# EasyEDA_SCH_BL28Z-3005ZSK04Y_K_Version_B.net
KiCad netlist of a schematic drawn in EasyEDA
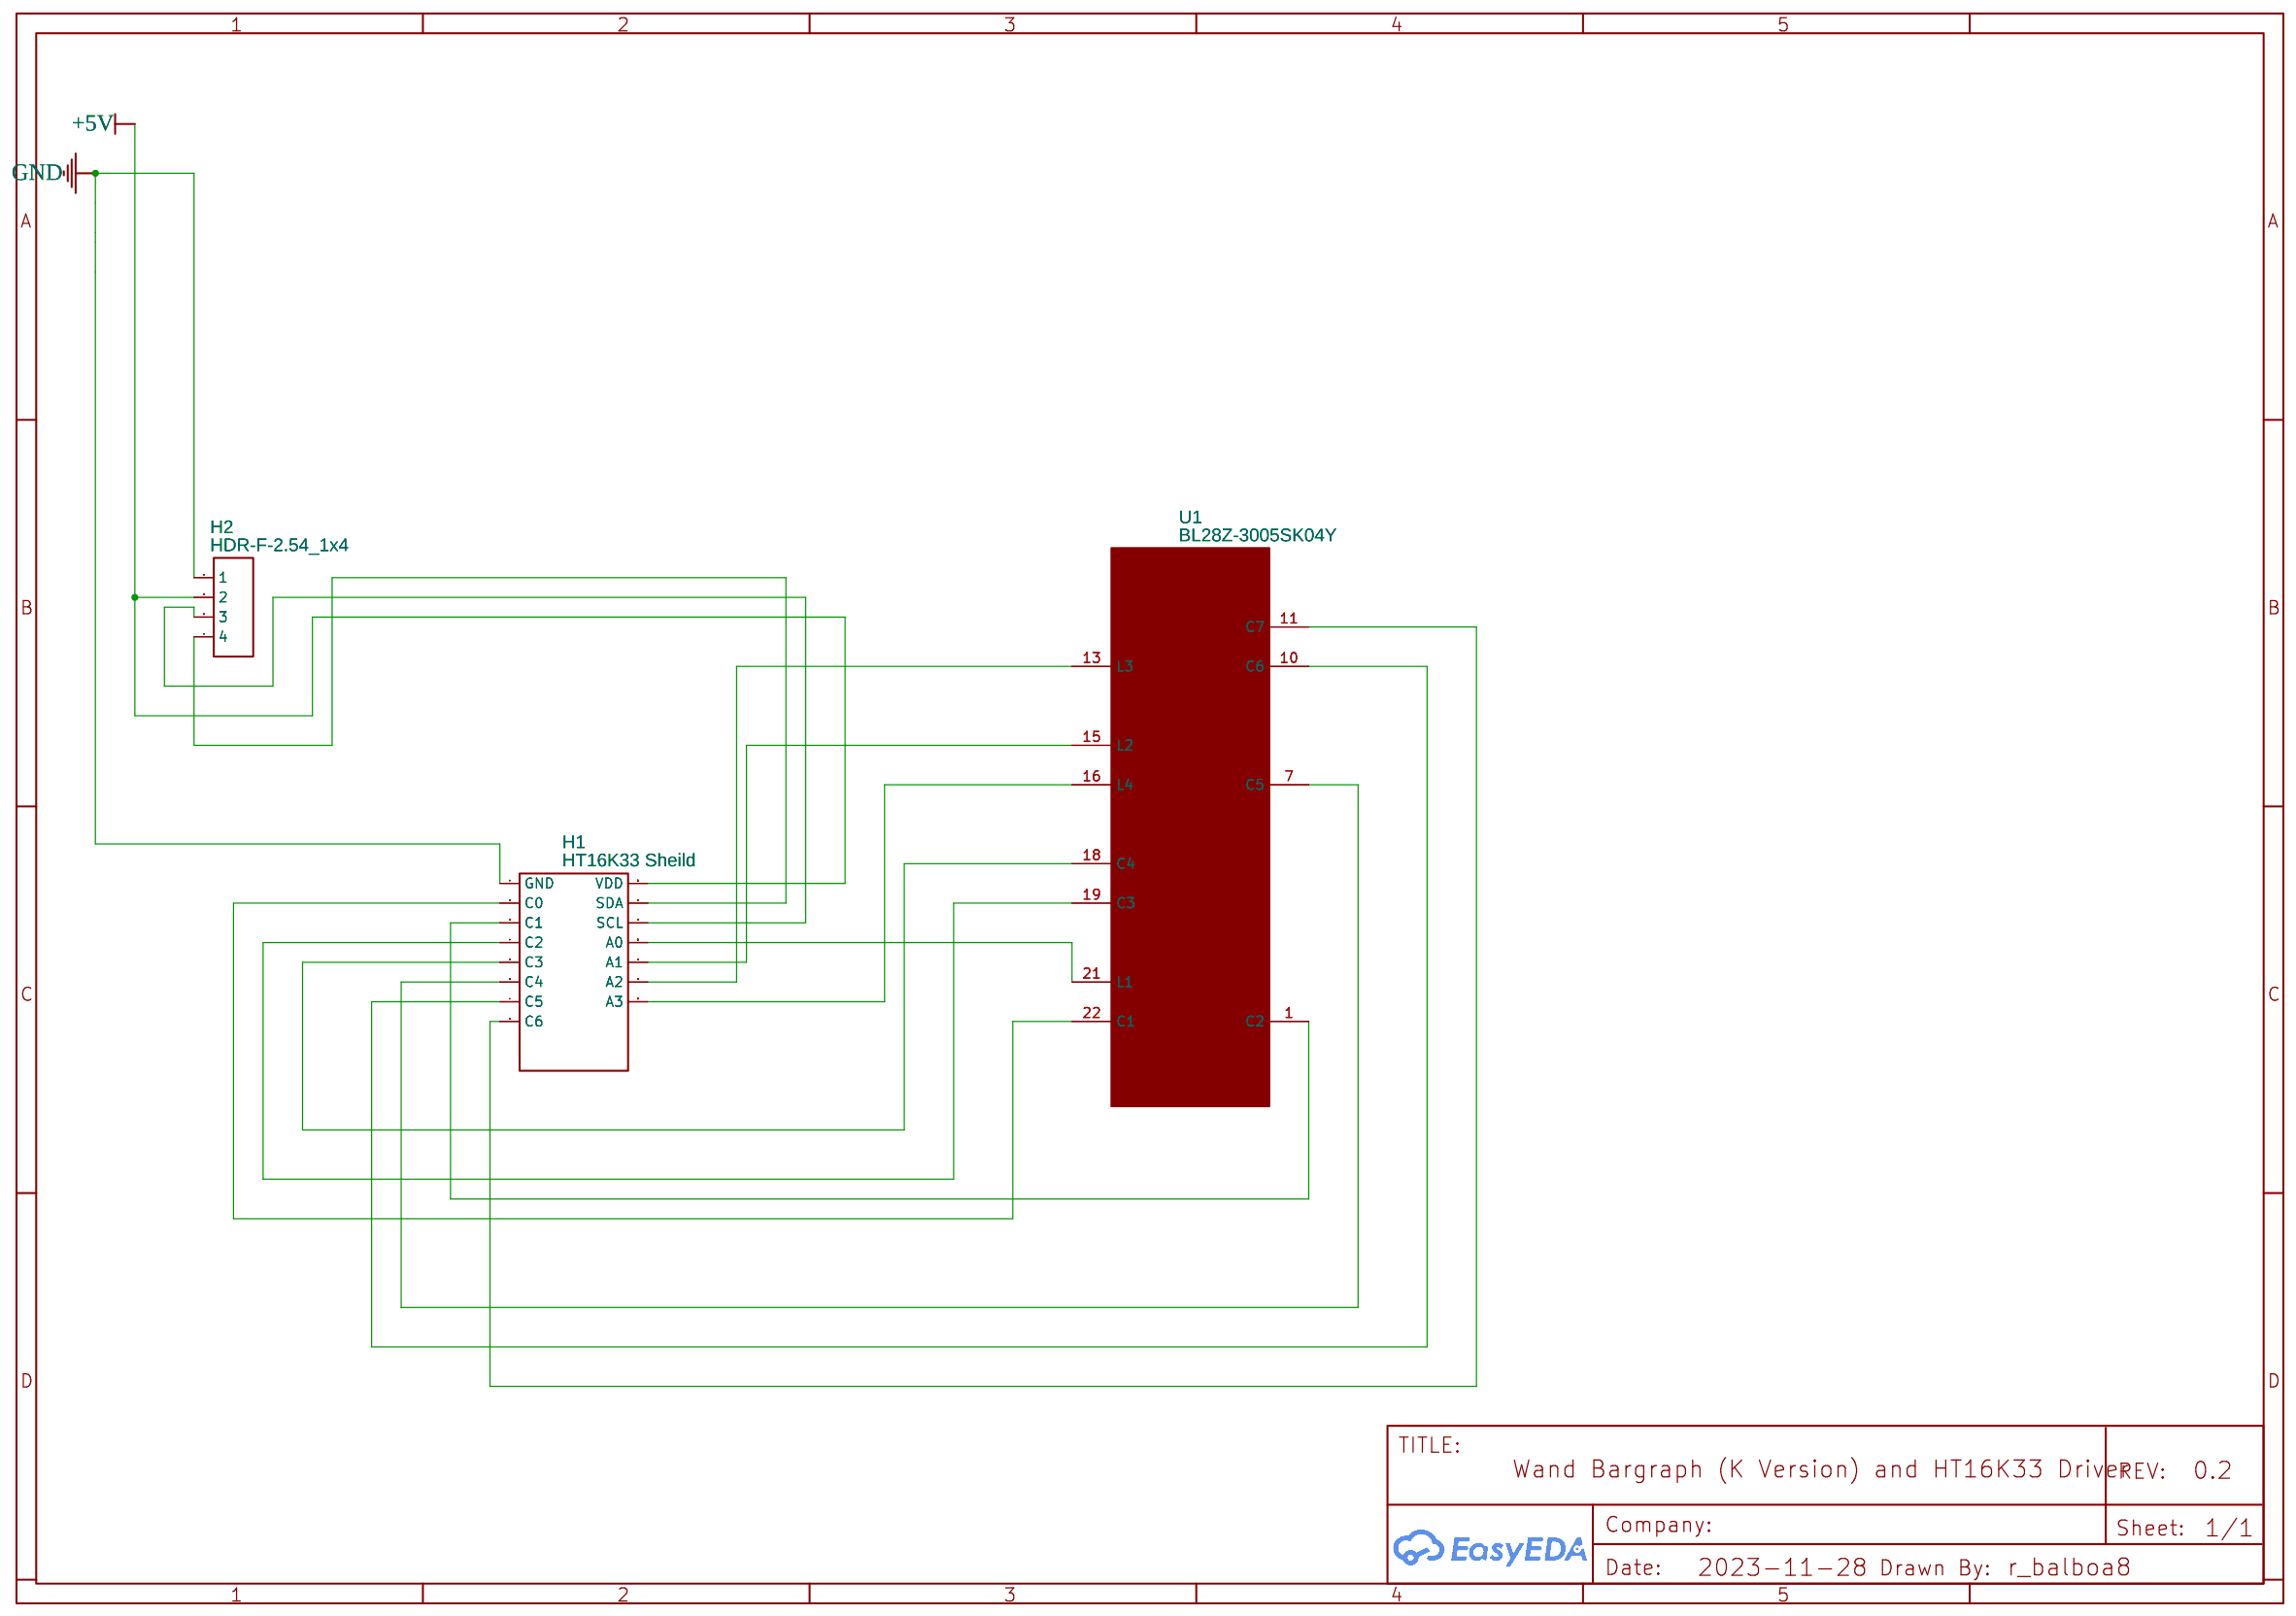
[diagram p0: schematic sheet]

(export (version "E")
  (design (tool "Eeschema 10.0.6"))
  (components
    (comp (ref "H1") (value "HT16K33 Sheild") (libsource (lib "") (part "HT16K33 BL28Z (Common Cathode)")))
    (comp (ref "H2") (value "HDR-F-2.54_1x4") (libsource (lib "") (part "HDR-F-2.54_1x4")))
    (comp (ref "U1")
      (value "BL28Z-3005SK04Y")
      (fields (field (name "Manufacturer Part") "BL28-3005SDK04") (field (name "Manufacturer") "BARMETER"))
      (libsource (lib "") (part "BL28Z-3005SA04Y"))
    )
  )
  (nets
    (net (code "1") (name "+5V") (class "Default")
      (node (ref "H1") (pin "28") (pinfunction "VDD_28") (pintype "unspecified"))
      (node (ref "H2") (pin "2") (pinfunction "2_2") (pintype "unspecified"))
    )
    (net (code "2") (name "GND") (class "Default")
      (node (ref "H1") (pin "1") (pinfunction "GND_1") (pintype "unspecified"))
      (node (ref "H2") (pin "1") (pinfunction "1_1") (pintype "unspecified"))
    )
    (net (code "3") (name "Net-(H1-A0)") (class "Default")
      (node (ref "H1") (pin "25") (pinfunction "A0_25") (pintype "unspecified"))
      (node (ref "U1") (pin "21") (pinfunction "L1_21") (pintype "unspecified"))
    )
    (net (code "4") (name "Net-(H1-A1)") (class "Default")
      (node (ref "H1") (pin "24") (pinfunction "A1_24") (pintype "unspecified"))
      (node (ref "U1") (pin "15") (pinfunction "L2_15") (pintype "unspecified"))
    )
    (net (code "5") (name "Net-(H1-A2)") (class "Default")
      (node (ref "H1") (pin "23") (pinfunction "A2_23") (pintype "unspecified"))
      (node (ref "U1") (pin "13") (pinfunction "L3_13") (pintype "unspecified"))
    )
    (net (code "6") (name "Net-(H1-A3)") (class "Default")
      (node (ref "H1") (pin "22") (pinfunction "A3_22") (pintype "unspecified"))
      (node (ref "U1") (pin "16") (pinfunction "L4_16") (pintype "unspecified"))
    )
    (net (code "7") (name "Net-(H1-C0)") (class "Default")
      (node (ref "H1") (pin "2") (pinfunction "C0_2") (pintype "unspecified"))
      (node (ref "U1") (pin "22") (pinfunction "C1_22") (pintype "unspecified"))
    )
    (net (code "8") (name "Net-(H1-C1)") (class "Default")
      (node (ref "H1") (pin "3") (pinfunction "C1_3") (pintype "unspecified"))
      (node (ref "U1") (pin "1") (pinfunction "C2_1") (pintype "unspecified"))
    )
    (net (code "9") (name "Net-(H1-C2)") (class "Default")
      (node (ref "H1") (pin "4") (pinfunction "C2_4") (pintype "unspecified"))
      (node (ref "U1") (pin "19") (pinfunction "C3_19") (pintype "unspecified"))
    )
    (net (code "10") (name "Net-(H1-C3)") (class "Default")
      (node (ref "H1") (pin "5") (pinfunction "C3_5") (pintype "unspecified"))
      (node (ref "U1") (pin "18") (pinfunction "C4_18") (pintype "unspecified"))
    )
    (net (code "11") (name "Net-(H1-C4)") (class "Default")
      (node (ref "H1") (pin "6") (pinfunction "C4_6") (pintype "unspecified"))
      (node (ref "U1") (pin "7") (pinfunction "C5_7") (pintype "unspecified"))
    )
    (net (code "12") (name "Net-(H1-C5)") (class "Default")
      (node (ref "H1") (pin "7") (pinfunction "C5_7") (pintype "unspecified"))
      (node (ref "U1") (pin "10") (pinfunction "C6_10") (pintype "unspecified"))
    )
    (net (code "13") (name "Net-(H1-C6)") (class "Default")
      (node (ref "H1") (pin "8") (pinfunction "C6_8") (pintype "unspecified"))
      (node (ref "U1") (pin "11") (pinfunction "C7_11") (pintype "unspecified"))
    )
    (net (code "14") (name "Net-(H1-SCL)") (class "Default")
      (node (ref "H1") (pin "26") (pinfunction "SCL_26") (pintype "unspecified"))
      (node (ref "H2") (pin "3") (pinfunction "3_3") (pintype "unspecified"))
    )
    (net (code "15") (name "Net-(H1-SDA)") (class "Default")
      (node (ref "H1") (pin "27") (pinfunction "SDA_27") (pintype "unspecified"))
      (node (ref "H2") (pin "4") (pinfunction "4_4") (pintype "unspecified"))
    )
  )
)
